# AnalogSimulator.net
KiCad netlist of a schematic drawn in EAGLE
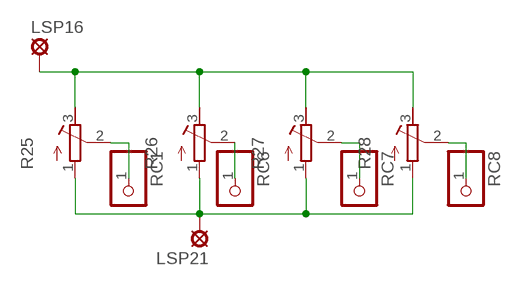
[diagram p0: schematic, sheet 1]

(export (version "E")
  (design (tool "Eeschema 10.0.6"))
  (components
    (comp (ref "LSP16")
      (value "LSP10")
      (footprint "eagle-import:LSP10")
      (libsource (lib "eagle-import") (part "LSP10"))
    )
    (comp (ref "LSP21")
      (value "LSP10")
      (footprint "eagle-import:LSP10")
      (libsource (lib "eagle-import") (part "LSP10"))
    )
    (comp (ref "R25")
      (value "R-TRIMM3339P")
      (footprint "eagle-import:RTRIM3339P")
      (libsource (lib "eagle-import") (part "R-TRIMM3339P"))
    )
    (comp (ref "R26")
      (value "R-TRIMM3339P")
      (footprint "eagle-import:RTRIM3339P")
      (libsource (lib "eagle-import") (part "R-TRIMM3339P"))
    )
    (comp (ref "R27")
      (value "R-TRIMM3339P")
      (footprint "eagle-import:RTRIM3339P")
      (libsource (lib "eagle-import") (part "R-TRIMM3339P"))
    )
    (comp (ref "R28")
      (value "R-TRIMM3339P")
      (footprint "eagle-import:RTRIM3339P")
      (libsource (lib "eagle-import") (part "R-TRIMM3339P"))
    )
    (comp (ref "RC1")
      (value "PINHD-1X1")
      (footprint "eagle-import:1X01")
      (libsource (lib "eagle-import") (part "PINHD-1X1"))
    )
    (comp (ref "RC6")
      (value "PINHD-1X1")
      (footprint "eagle-import:1X01")
      (libsource (lib "eagle-import") (part "PINHD-1X1"))
    )
    (comp (ref "RC7")
      (value "PINHD-1X1")
      (footprint "eagle-import:1X01")
      (libsource (lib "eagle-import") (part "PINHD-1X1"))
    )
    (comp (ref "RC8")
      (value "PINHD-1X1")
      (footprint "eagle-import:1X01")
      (libsource (lib "eagle-import") (part "PINHD-1X1"))
    )
  )
  (nets
    (net (code "1") (name "Net-(R25-A)") (class "Default")
      (node (ref "LSP21") (pin "MP") (pinfunction "MP_MP") (pintype "passive"))
      (node (ref "R25") (pin "1") (pinfunction "A_1") (pintype "passive"))
      (node (ref "R26") (pin "1") (pinfunction "A_1") (pintype "passive"))
      (node (ref "R27") (pin "1") (pinfunction "A_1") (pintype "passive"))
      (node (ref "R28") (pin "1") (pinfunction "A_1") (pintype "passive"))
    )
    (net (code "2") (name "Net-(R25-E)") (class "Default")
      (node (ref "LSP16") (pin "MP") (pinfunction "MP_MP") (pintype "passive"))
      (node (ref "R25") (pin "3") (pinfunction "E_3") (pintype "passive"))
      (node (ref "R26") (pin "3") (pinfunction "E_3") (pintype "passive"))
      (node (ref "R27") (pin "3") (pinfunction "E_3") (pintype "passive"))
      (node (ref "R28") (pin "3") (pinfunction "E_3") (pintype "passive"))
    )
    (net (code "3") (name "Net-(R25-S)") (class "Default")
      (node (ref "R25") (pin "2") (pinfunction "S_2") (pintype "passive"))
      (node (ref "RC1") (pin "1") (pinfunction "1_1") (pintype "passive"))
    )
    (net (code "4") (name "Net-(R26-S)") (class "Default")
      (node (ref "R26") (pin "2") (pinfunction "S_2") (pintype "passive"))
      (node (ref "RC6") (pin "1") (pinfunction "1_1") (pintype "passive"))
    )
    (net (code "5") (name "Net-(R27-S)") (class "Default")
      (node (ref "R27") (pin "2") (pinfunction "S_2") (pintype "passive"))
      (node (ref "RC7") (pin "1") (pinfunction "1_1") (pintype "passive"))
    )
    (net (code "6") (name "Net-(R28-S)") (class "Default")
      (node (ref "R28") (pin "2") (pinfunction "S_2") (pintype "passive"))
      (node (ref "RC8") (pin "1") (pinfunction "1_1") (pintype "passive"))
    )
  )
)
